# SuperCapV3Power.net
KiCad netlist of a schematic drawn in Altium Designer
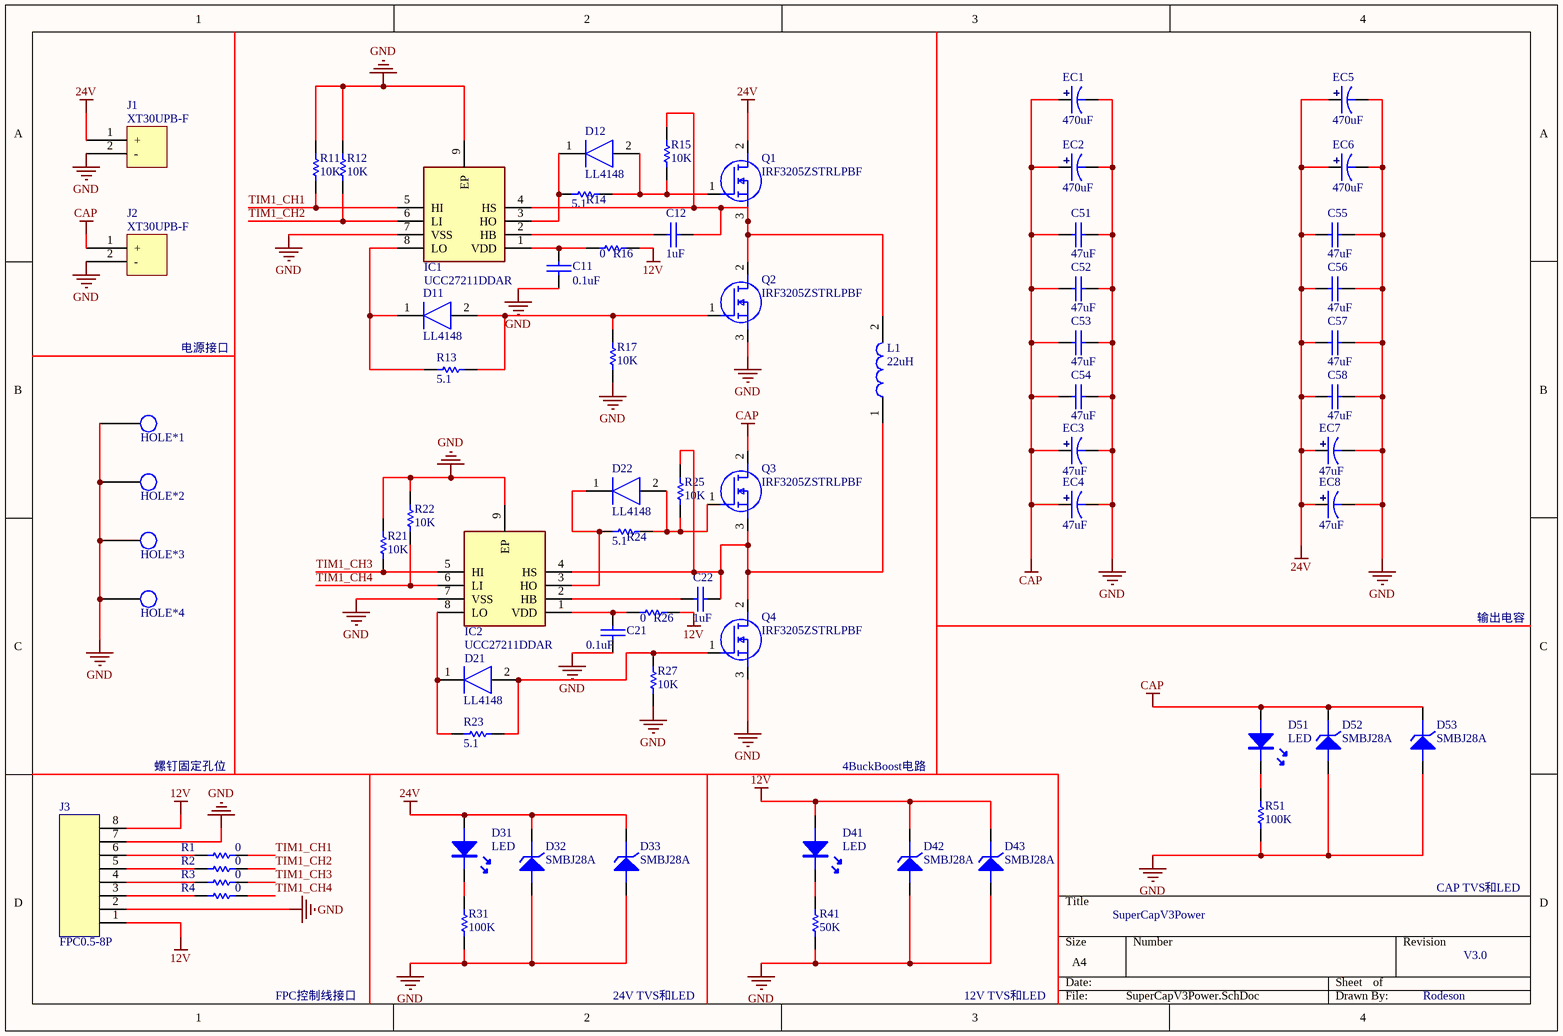
[diagram p0: SuperCapV3Power.SchDoc]

(export (version "E")
  (design (tool "Eeschema 10.0.6"))
  (components
    (comp (ref "C11")
      (value "0.1uF")
      (footprint "0603C")
      (description "无极性电容")
      (libsource (lib "电容") (part "CAP"))
    )
    (comp (ref "C12")
      (value "1uF")
      (footprint "0603C")
      (description "无极性电容")
      (libsource (lib "电容") (part "CAP"))
    )
    (comp (ref "C21")
      (value "0.1uF")
      (footprint "0603C")
      (description "无极性电容")
      (libsource (lib "电容") (part "CAP"))
    )
    (comp (ref "C22")
      (value "1uF")
      (footprint "0603C")
      (description "无极性电容")
      (libsource (lib "电容") (part "CAP"))
    )
    (comp (ref "C51")
      (value "47uF")
      (footprint "1812C")
      (description "无极性电容")
      (libsource (lib "电容") (part "CAP"))
    )
    (comp (ref "C52")
      (value "47uF")
      (footprint "1812C")
      (description "无极性电容")
      (libsource (lib "电容") (part "CAP"))
    )
    (comp (ref "C53")
      (value "47uF")
      (footprint "1812C")
      (description "无极性电容")
      (libsource (lib "电容") (part "CAP"))
    )
    (comp (ref "C54")
      (value "47uF")
      (footprint "1812C")
      (description "无极性电容")
      (libsource (lib "电容") (part "CAP"))
    )
    (comp (ref "C55")
      (value "47uF")
      (footprint "1812C")
      (description "无极性电容")
      (libsource (lib "电容") (part "CAP"))
    )
    (comp (ref "C56")
      (value "47uF")
      (footprint "1812C")
      (description "无极性电容")
      (libsource (lib "电容") (part "CAP"))
    )
    (comp (ref "C57")
      (value "47uF")
      (footprint "1812C")
      (description "无极性电容")
      (libsource (lib "电容") (part "CAP"))
    )
    (comp (ref "C58")
      (value "47uF")
      (footprint "1812C")
      (description "无极性电容")
      (libsource (lib "电容") (part "CAP"))
    )
    (comp (ref "D11")
      (value "LL4148")
      (footprint "SamacSys:FDLL4448")
      (description "Diode")
      (fields (field (name "MOUSER PART NUMBER") "512-LL4148"))
      (libsource (lib "*") (part "LL4148"))
    )
    (comp (ref "D12")
      (value "LL4148")
      (footprint "SamacSys:FDLL4448")
      (description "Diode")
      (fields (field (name "MOUSER PART NUMBER") "512-LL4148"))
      (libsource (lib "*") (part "LL4148"))
    )
    (comp (ref "D21")
      (value "LL4148")
      (footprint "SamacSys:FDLL4448")
      (description "Diode")
      (fields (field (name "MOUSER PART NUMBER") "512-LL4148"))
      (libsource (lib "*") (part "LL4148"))
    )
    (comp (ref "D22")
      (value "LL4148")
      (footprint "SamacSys:FDLL4448")
      (description "Diode")
      (fields (field (name "MOUSER PART NUMBER") "512-LL4148"))
      (libsource (lib "*") (part "LL4148"))
    )
    (comp (ref "D31") (value "LED") (footprint "LED-0603G") (libsource (lib "SuperCap_V2") (part "LED")))
    (comp (ref "D32")
      (value "SMBJ28A")
      (footprint "SMC/DO-214AB")
      (description "稳压二极管")
      (libsource (lib "二极管") (part "DIODE ZENER"))
    )
    (comp (ref "D33")
      (value "SMBJ28A")
      (footprint "SMC/DO-214AB")
      (description "稳压二极管")
      (libsource (lib "二极管") (part "DIODE ZENER"))
    )
    (comp (ref "D41") (value "LED") (footprint "LED-0603G") (libsource (lib "SuperCap_V2") (part "LED")))
    (comp (ref "D42")
      (value "SMBJ28A")
      (footprint "SMC/DO-214AB")
      (description "稳压二极管")
      (libsource (lib "二极管") (part "DIODE ZENER"))
    )
    (comp (ref "D43")
      (value "SMBJ28A")
      (footprint "SMC/DO-214AB")
      (description "稳压二极管")
      (libsource (lib "二极管") (part "DIODE ZENER"))
    )
    (comp (ref "D51") (value "LED") (footprint "LED-0603G") (libsource (lib "SuperCap_V2") (part "LED")))
    (comp (ref "D52")
      (value "SMBJ28A")
      (footprint "SMC/DO-214AB")
      (description "稳压二极管")
      (libsource (lib "二极管") (part "DIODE ZENER"))
    )
    (comp (ref "D53")
      (value "SMBJ28A")
      (footprint "SMC/DO-214AB")
      (description "稳压二极管")
      (libsource (lib "二极管") (part "DIODE ZENER"))
    )
    (comp (ref "EC1")
      (value "470uF")
      (footprint "DIP-EC5.0X10X16-A")
      (description "直插电解电容")
      (libsource (lib "电容") (part "DIP_ECAP"))
    )
    (comp (ref "EC2")
      (value "470uF")
      (footprint "DIP-EC5.0X10X16-A")
      (description "直插电解电容")
      (libsource (lib "电容") (part "DIP_ECAP"))
    )
    (comp (ref "EC3")
      (value "47uF")
      (footprint "SMD-EC10X10X10")
      (description "贴片电解电容")
      (libsource (lib "电容") (part "SMD_ECAP"))
    )
    (comp (ref "EC4")
      (value "47uF")
      (footprint "SMD-EC10X10X10")
      (description "贴片电解电容")
      (libsource (lib "电容") (part "SMD_ECAP"))
    )
    (comp (ref "EC5")
      (value "470uF")
      (footprint "DIP-EC5.0X10X16-A")
      (description "直插电解电容")
      (libsource (lib "电容") (part "DIP_ECAP"))
    )
    (comp (ref "EC6")
      (value "470uF")
      (footprint "DIP-EC5.0X10X16-A")
      (description "直插电解电容")
      (libsource (lib "电容") (part "DIP_ECAP"))
    )
    (comp (ref "EC7")
      (value "47uF")
      (footprint "SMD-EC10X10X10")
      (description "贴片电解电容")
      (libsource (lib "电容") (part "SMD_ECAP"))
    )
    (comp (ref "EC8")
      (value "47uF")
      (footprint "SMD-EC10X10X10")
      (description "贴片电解电容")
      (libsource (lib "电容") (part "SMD_ECAP"))
    )
    (comp (ref "HOLE*1") (value "Hole") (footprint "M3") (libsource (lib "SuperCap_V2") (part "Hole")))
    (comp (ref "HOLE*2") (value "Hole") (footprint "M3") (libsource (lib "SuperCap_V2") (part "Hole")))
    (comp (ref "HOLE*3") (value "Hole") (footprint "M3") (libsource (lib "SuperCap_V2") (part "Hole")))
    (comp (ref "HOLE*4") (value "Hole") (footprint "M3") (libsource (lib "SuperCap_V2") (part "Hole")))
    (comp (ref "IC1")
      (value "UCC27211DDAR")
      (footprint "SamacSys:SOIC127P600X170-9N")
      (description "Integrated Circuit")
      (fields (field (name "MOUSER PART NUMBER") "595-UCC27211DDAR"))
      (libsource (lib "SamacSys") (part "UCC27211DDAR"))
    )
    (comp (ref "IC2")
      (value "UCC27211DDAR")
      (footprint "SamacSys:SOIC127P600X170-9N")
      (description "Integrated Circuit")
      (fields (field (name "MOUSER PART NUMBER") "595-UCC27211DDAR"))
      (libsource (lib "SamacSys") (part "UCC27211DDAR"))
    )
    (comp (ref "J1")
      (value "XT30UPB-F")
      (footprint "XT30UPB-F")
      (libsource (lib "powerdesigner") (part "XT30UPB-F"))
    )
    (comp (ref "J2")
      (value "XT30UPB-F")
      (footprint "XT30UPB-F")
      (libsource (lib "powerdesigner") (part "XT30UPB-F"))
    )
    (comp (ref "J3")
      (value "FPC0.5-8P")
      (footprint "FPC0.5-8P")
      (description "贴片")
      (libsource (lib "FPC") (part "FPC0.5-8P"))
    )
    (comp (ref "L1")
      (value "22uH")
      (footprint "SamacSys:INDPM180170X700N")
      (description "Inductor")
      (fields (field (name "MANUFACTURER_PART_NUMBER") "BCIHP1770-100M"))
      (libsource (lib "SuperCap_V2") (part "BCIHP1770-100M"))
    )
    (comp (ref "Q1")
      (value "IRF3205ZSTRLPBF")
      (footprint "SamacSys:IDB30E60")
      (description "MOSFET (N-Channel)")
      (fields (field (name "MOUSER PART NUMBER") "942-IRF3205ZSTRLPBF"))
      (libsource (lib "SamacSys") (part "IRF3205ZSTRLPBF"))
    )
    (comp (ref "Q2")
      (value "IRF3205ZSTRLPBF")
      (footprint "SamacSys:IDB30E60")
      (description "MOSFET (N-Channel)")
      (fields (field (name "MOUSER PART NUMBER") "942-IRF3205ZSTRLPBF"))
      (libsource (lib "SamacSys") (part "IRF3205ZSTRLPBF"))
    )
    (comp (ref "Q3")
      (value "IRF3205ZSTRLPBF")
      (footprint "SamacSys:IDB30E60")
      (description "MOSFET (N-Channel)")
      (fields (field (name "MOUSER PART NUMBER") "942-IRF3205ZSTRLPBF"))
      (libsource (lib "SamacSys") (part "IRF3205ZSTRLPBF"))
    )
    (comp (ref "Q4")
      (value "IRF3205ZSTRLPBF")
      (footprint "SamacSys:IDB30E60")
      (description "MOSFET (N-Channel)")
      (fields (field (name "MOUSER PART NUMBER") "942-IRF3205ZSTRLPBF"))
      (libsource (lib "SamacSys") (part "IRF3205ZSTRLPBF"))
    )
    (comp (ref "R1") (value "0") (footprint "0603R") (libsource (lib "电阻") (part "RES")))
    (comp (ref "R2") (value "0") (footprint "0603R") (libsource (lib "电阻") (part "RES")))
    (comp (ref "R3") (value "0") (footprint "0603R") (libsource (lib "电阻") (part "RES")))
    (comp (ref "R4") (value "0") (footprint "0603R") (libsource (lib "电阻") (part "RES")))
    (comp (ref "R11") (value "10K") (footprint "0603R") (libsource (lib "电阻") (part "RES")))
    (comp (ref "R12") (value "10K") (footprint "0603R") (libsource (lib "电阻") (part "RES")))
    (comp (ref "R13") (value "5.1") (footprint "0603R") (libsource (lib "电阻") (part "RES")))
    (comp (ref "R14") (value "5.1") (footprint "0603R") (libsource (lib "电阻") (part "RES")))
    (comp (ref "R15") (value "10K") (footprint "0603R") (libsource (lib "电阻") (part "RES")))
    (comp (ref "R16") (value "0") (footprint "0603R") (libsource (lib "电阻") (part "RES")))
    (comp (ref "R17") (value "10K") (footprint "0603R") (libsource (lib "电阻") (part "RES")))
    (comp (ref "R21") (value "10K") (footprint "0603R") (libsource (lib "电阻") (part "RES")))
    (comp (ref "R22") (value "10K") (footprint "0603R") (libsource (lib "电阻") (part "RES")))
    (comp (ref "R23") (value "5.1") (footprint "0603R") (libsource (lib "电阻") (part "RES")))
    (comp (ref "R24") (value "5.1") (footprint "0603R") (libsource (lib "电阻") (part "RES")))
    (comp (ref "R25") (value "10K") (footprint "0603R") (libsource (lib "电阻") (part "RES")))
    (comp (ref "R26") (value "0") (footprint "0603R") (libsource (lib "电阻") (part "RES")))
    (comp (ref "R27") (value "10K") (footprint "0603R") (libsource (lib "电阻") (part "RES")))
    (comp (ref "R31") (value "100K") (footprint "0603R") (libsource (lib "电阻") (part "RES")))
    (comp (ref "R41") (value "50K") (footprint "0603R") (libsource (lib "电阻") (part "RES")))
    (comp (ref "R51") (value "100K") (footprint "0603R") (libsource (lib "电阻") (part "RES")))
  )
  (nets
    (net (code "1") (name "/TIM1_CH1") (class "Default")
      (node (ref "IC1") (pin "5") (pinfunction "HI_5") (pintype "passive"))
      (node (ref "R1") (pin "2") (pinfunction "2_2") (pintype "passive"))
      (node (ref "R11") (pin "1") (pinfunction "1_1") (pintype "passive"))
    )
    (net (code "2") (name "/TIM1_CH2") (class "Default")
      (node (ref "IC1") (pin "6") (pinfunction "LI_6") (pintype "passive"))
      (node (ref "R12") (pin "1") (pinfunction "1_1") (pintype "passive"))
      (node (ref "R2") (pin "2") (pinfunction "2_2") (pintype "passive"))
    )
    (net (code "3") (name "/TIM1_CH3") (class "Default")
      (node (ref "IC2") (pin "5") (pinfunction "HI_5") (pintype "passive"))
      (node (ref "R21") (pin "1") (pinfunction "1_1") (pintype "passive"))
      (node (ref "R3") (pin "2") (pinfunction "2_2") (pintype "passive"))
    )
    (net (code "4") (name "/TIM1_CH4") (class "Default")
      (node (ref "IC2") (pin "6") (pinfunction "LI_6") (pintype "passive"))
      (node (ref "R22") (pin "1") (pinfunction "1_1") (pintype "passive"))
      (node (ref "R4") (pin "2") (pinfunction "2_2") (pintype "passive"))
    )
    (net (code "5") (name "12V") (class "Default")
      (node (ref "D41") (pin "A") (pinfunction "A_A") (pintype "passive"))
      (node (ref "D42") (pin "K") (pinfunction "K_K") (pintype "passive"))
      (node (ref "D43") (pin "K") (pinfunction "K_K") (pintype "passive"))
      (node (ref "J3") (pin "1") (pinfunction "1_1") (pintype "passive"))
      (node (ref "J3") (pin "8") (pinfunction "8_8") (pintype "passive"))
      (node (ref "R16") (pin "2") (pinfunction "2_2") (pintype "passive"))
      (node (ref "R26") (pin "2") (pinfunction "2_2") (pintype "passive"))
    )
    (net (code "6") (name "24V") (class "Default")
      (node (ref "C55") (pin "1") (pinfunction "1_1") (pintype "passive"))
      (node (ref "C56") (pin "1") (pinfunction "1_1") (pintype "passive"))
      (node (ref "C57") (pin "1") (pinfunction "1_1") (pintype "passive"))
      (node (ref "C58") (pin "1") (pinfunction "1_1") (pintype "passive"))
      (node (ref "D31") (pin "A") (pinfunction "A_A") (pintype "passive"))
      (node (ref "D32") (pin "K") (pinfunction "K_K") (pintype "passive"))
      (node (ref "D33") (pin "K") (pinfunction "K_K") (pintype "passive"))
      (node (ref "EC5") (pin "1") (pinfunction "1_1") (pintype "passive"))
      (node (ref "EC6") (pin "1") (pinfunction "1_1") (pintype "passive"))
      (node (ref "EC7") (pin "1") (pinfunction "1_1") (pintype "passive"))
      (node (ref "EC8") (pin "1") (pinfunction "1_1") (pintype "passive"))
      (node (ref "J1") (pin "1") (pinfunction "+_1") (pintype "passive"))
      (node (ref "Q1") (pin "2") (pinfunction "D_2") (pintype "passive"))
    )
    (net (code "7") (name "CAP") (class "Default")
      (node (ref "C51") (pin "1") (pinfunction "1_1") (pintype "passive"))
      (node (ref "C52") (pin "1") (pinfunction "1_1") (pintype "passive"))
      (node (ref "C53") (pin "1") (pinfunction "1_1") (pintype "passive"))
      (node (ref "C54") (pin "1") (pinfunction "1_1") (pintype "passive"))
      (node (ref "D51") (pin "A") (pinfunction "A_A") (pintype "passive"))
      (node (ref "D52") (pin "K") (pinfunction "K_K") (pintype "passive"))
      (node (ref "D53") (pin "K") (pinfunction "K_K") (pintype "passive"))
      (node (ref "EC1") (pin "1") (pinfunction "1_1") (pintype "passive"))
      (node (ref "EC2") (pin "1") (pinfunction "1_1") (pintype "passive"))
      (node (ref "EC3") (pin "1") (pinfunction "1_1") (pintype "passive"))
      (node (ref "EC4") (pin "1") (pinfunction "1_1") (pintype "passive"))
      (node (ref "J2") (pin "1") (pinfunction "+_1") (pintype "passive"))
      (node (ref "Q3") (pin "2") (pinfunction "D_2") (pintype "passive"))
    )
    (net (code "8") (name "GND") (class "Default")
      (node (ref "C11") (pin "1") (pinfunction "1_1") (pintype "passive"))
      (node (ref "C21") (pin "1") (pinfunction "1_1") (pintype "passive"))
      (node (ref "C51") (pin "2") (pinfunction "2_2") (pintype "passive"))
      (node (ref "C52") (pin "2") (pinfunction "2_2") (pintype "passive"))
      (node (ref "C53") (pin "2") (pinfunction "2_2") (pintype "passive"))
      (node (ref "C54") (pin "2") (pinfunction "2_2") (pintype "passive"))
      (node (ref "C55") (pin "2") (pinfunction "2_2") (pintype "passive"))
      (node (ref "C56") (pin "2") (pinfunction "2_2") (pintype "passive"))
      (node (ref "C57") (pin "2") (pinfunction "2_2") (pintype "passive"))
      (node (ref "C58") (pin "2") (pinfunction "2_2") (pintype "passive"))
      (node (ref "D32") (pin "A") (pinfunction "A_A") (pintype "passive"))
      (node (ref "D33") (pin "A") (pinfunction "A_A") (pintype "passive"))
      (node (ref "D42") (pin "A") (pinfunction "A_A") (pintype "passive"))
      (node (ref "D43") (pin "A") (pinfunction "A_A") (pintype "passive"))
      (node (ref "D52") (pin "A") (pinfunction "A_A") (pintype "passive"))
      (node (ref "D53") (pin "A") (pinfunction "A_A") (pintype "passive"))
      (node (ref "EC1") (pin "2") (pinfunction "2_2") (pintype "passive"))
      (node (ref "EC2") (pin "2") (pinfunction "2_2") (pintype "passive"))
      (node (ref "EC3") (pin "2") (pinfunction "2_2") (pintype "passive"))
      (node (ref "EC4") (pin "2") (pinfunction "2_2") (pintype "passive"))
      (node (ref "EC5") (pin "2") (pinfunction "2_2") (pintype "passive"))
      (node (ref "EC6") (pin "2") (pinfunction "2_2") (pintype "passive"))
      (node (ref "EC7") (pin "2") (pinfunction "2_2") (pintype "passive"))
      (node (ref "EC8") (pin "2") (pinfunction "2_2") (pintype "passive"))
      (node (ref "HOLE*1") (pin "1") (pinfunction "1_1") (pintype "passive"))
      (node (ref "HOLE*2") (pin "1") (pinfunction "1_1") (pintype "passive"))
      (node (ref "HOLE*3") (pin "1") (pinfunction "1_1") (pintype "passive"))
      (node (ref "HOLE*4") (pin "1") (pinfunction "1_1") (pintype "passive"))
      (node (ref "IC1") (pin "7") (pinfunction "VSS_7") (pintype "passive"))
      (node (ref "IC1") (pin "9") (pinfunction "EP_9") (pintype "passive"))
      (node (ref "IC2") (pin "7") (pinfunction "VSS_7") (pintype "passive"))
      (node (ref "IC2") (pin "9") (pinfunction "EP_9") (pintype "passive"))
      (node (ref "J1") (pin "2") (pinfunction "-_2") (pintype "passive"))
      (node (ref "J2") (pin "2") (pinfunction "-_2") (pintype "passive"))
      (node (ref "J3") (pin "2") (pinfunction "2_2") (pintype "passive"))
      (node (ref "J3") (pin "7") (pinfunction "7_7") (pintype "passive"))
      (node (ref "Q2") (pin "3") (pinfunction "S_3") (pintype "passive"))
      (node (ref "Q4") (pin "3") (pinfunction "S_3") (pintype "passive"))
      (node (ref "R11") (pin "2") (pinfunction "2_2") (pintype "passive"))
      (node (ref "R12") (pin "2") (pinfunction "2_2") (pintype "passive"))
      (node (ref "R17") (pin "1") (pinfunction "1_1") (pintype "passive"))
      (node (ref "R21") (pin "2") (pinfunction "2_2") (pintype "passive"))
      (node (ref "R22") (pin "2") (pinfunction "2_2") (pintype "passive"))
      (node (ref "R27") (pin "1") (pinfunction "1_1") (pintype "passive"))
      (node (ref "R31") (pin "1") (pinfunction "1_1") (pintype "passive"))
      (node (ref "R41") (pin "1") (pinfunction "1_1") (pintype "passive"))
      (node (ref "R51") (pin "1") (pinfunction "1_1") (pintype "passive"))
    )
    (net (code "9") (name "Net-(D11-A)") (class "Default")
      (node (ref "D11") (pin "2") (pinfunction "A_2") (pintype "passive"))
      (node (ref "Q2") (pin "1") (pinfunction "G_1") (pintype "passive"))
      (node (ref "R13") (pin "2") (pinfunction "2_2") (pintype "passive"))
      (node (ref "R17") (pin "2") (pinfunction "2_2") (pintype "passive"))
    )
    (net (code "10") (name "Net-(D11-K)") (class "Default")
      (node (ref "D11") (pin "1") (pinfunction "K_1") (pintype "passive"))
      (node (ref "IC1") (pin "8") (pinfunction "LO_8") (pintype "passive"))
      (node (ref "R13") (pin "1") (pinfunction "1_1") (pintype "passive"))
    )
    (net (code "11") (name "Net-(D12-A)") (class "Default")
      (node (ref "D12") (pin "2") (pinfunction "A_2") (pintype "passive"))
      (node (ref "Q1") (pin "1") (pinfunction "G_1") (pintype "passive"))
      (node (ref "R14") (pin "2") (pinfunction "2_2") (pintype "passive"))
      (node (ref "R15") (pin "1") (pinfunction "1_1") (pintype "passive"))
    )
    (net (code "12") (name "Net-(D12-K)") (class "Default")
      (node (ref "D12") (pin "1") (pinfunction "K_1") (pintype "passive"))
      (node (ref "IC1") (pin "3") (pinfunction "HO_3") (pintype "passive"))
      (node (ref "R14") (pin "1") (pinfunction "1_1") (pintype "passive"))
    )
    (net (code "13") (name "Net-(D21-A)") (class "Default")
      (node (ref "D21") (pin "2") (pinfunction "A_2") (pintype "passive"))
      (node (ref "Q4") (pin "1") (pinfunction "G_1") (pintype "passive"))
      (node (ref "R23") (pin "2") (pinfunction "2_2") (pintype "passive"))
      (node (ref "R27") (pin "2") (pinfunction "2_2") (pintype "passive"))
    )
    (net (code "14") (name "Net-(D21-K)") (class "Default")
      (node (ref "D21") (pin "1") (pinfunction "K_1") (pintype "passive"))
      (node (ref "IC2") (pin "8") (pinfunction "LO_8") (pintype "passive"))
      (node (ref "R23") (pin "1") (pinfunction "1_1") (pintype "passive"))
    )
    (net (code "15") (name "Net-(D22-A)") (class "Default")
      (node (ref "D22") (pin "2") (pinfunction "A_2") (pintype "passive"))
      (node (ref "Q3") (pin "1") (pinfunction "G_1") (pintype "passive"))
      (node (ref "R24") (pin "2") (pinfunction "2_2") (pintype "passive"))
      (node (ref "R25") (pin "1") (pinfunction "1_1") (pintype "passive"))
    )
    (net (code "16") (name "Net-(D22-K)") (class "Default")
      (node (ref "D22") (pin "1") (pinfunction "K_1") (pintype "passive"))
      (node (ref "IC2") (pin "3") (pinfunction "HO_3") (pintype "passive"))
      (node (ref "R24") (pin "1") (pinfunction "1_1") (pintype "passive"))
    )
    (net (code "17") (name "Net-(D31-PadK)") (class "Default")
      (node (ref "D31") (pin "K") (pinfunction "K_K") (pintype "passive"))
      (node (ref "R31") (pin "2") (pinfunction "2_2") (pintype "passive"))
    )
    (net (code "18") (name "Net-(D41-PadK)") (class "Default")
      (node (ref "D41") (pin "K") (pinfunction "K_K") (pintype "passive"))
      (node (ref "R41") (pin "2") (pinfunction "2_2") (pintype "passive"))
    )
    (net (code "19") (name "Net-(D51-PadK)") (class "Default")
      (node (ref "D51") (pin "K") (pinfunction "K_K") (pintype "passive"))
      (node (ref "R51") (pin "2") (pinfunction "2_2") (pintype "passive"))
    )
    (net (code "20") (name "Net-(IC1-HB)") (class "Default")
      (node (ref "C12") (pin "2") (pinfunction "2_2") (pintype "passive"))
      (node (ref "IC1") (pin "2") (pinfunction "HB_2") (pintype "passive"))
    )
    (net (code "21") (name "Net-(IC1-HS)") (class "Default")
      (node (ref "C12") (pin "1") (pinfunction "1_1") (pintype "passive"))
      (node (ref "IC1") (pin "4") (pinfunction "HS_4") (pintype "passive"))
      (node (ref "L1") (pin "2") (pinfunction "2_2") (pintype "passive"))
      (node (ref "Q1") (pin "3") (pinfunction "S_3") (pintype "passive"))
      (node (ref "Q2") (pin "2") (pinfunction "D_2") (pintype "passive"))
      (node (ref "R15") (pin "2") (pinfunction "2_2") (pintype "passive"))
    )
    (net (code "22") (name "Net-(IC1-VDD)") (class "Default")
      (node (ref "C11") (pin "2") (pinfunction "2_2") (pintype "passive"))
      (node (ref "IC1") (pin "1") (pinfunction "VDD_1") (pintype "passive"))
      (node (ref "R16") (pin "1") (pinfunction "1_1") (pintype "passive"))
    )
    (net (code "23") (name "Net-(IC2-HB)") (class "Default")
      (node (ref "C22") (pin "2") (pinfunction "2_2") (pintype "passive"))
      (node (ref "IC2") (pin "2") (pinfunction "HB_2") (pintype "passive"))
    )
    (net (code "24") (name "Net-(IC2-HS)") (class "Default")
      (node (ref "C22") (pin "1") (pinfunction "1_1") (pintype "passive"))
      (node (ref "IC2") (pin "4") (pinfunction "HS_4") (pintype "passive"))
      (node (ref "L1") (pin "1") (pinfunction "1_1") (pintype "passive"))
      (node (ref "Q3") (pin "3") (pinfunction "S_3") (pintype "passive"))
      (node (ref "Q4") (pin "2") (pinfunction "D_2") (pintype "passive"))
      (node (ref "R25") (pin "2") (pinfunction "2_2") (pintype "passive"))
    )
    (net (code "25") (name "Net-(IC2-VDD)") (class "Default")
      (node (ref "C21") (pin "2") (pinfunction "2_2") (pintype "passive"))
      (node (ref "IC2") (pin "1") (pinfunction "VDD_1") (pintype "passive"))
      (node (ref "R26") (pin "1") (pinfunction "1_1") (pintype "passive"))
    )
    (net (code "26") (name "Net-(J3-Pad3)") (class "Default")
      (node (ref "J3") (pin "3") (pinfunction "3_3") (pintype "passive"))
      (node (ref "R4") (pin "1") (pinfunction "1_1") (pintype "passive"))
    )
    (net (code "27") (name "Net-(J3-Pad4)") (class "Default")
      (node (ref "J3") (pin "4") (pinfunction "4_4") (pintype "passive"))
      (node (ref "R3") (pin "1") (pinfunction "1_1") (pintype "passive"))
    )
    (net (code "28") (name "Net-(J3-Pad5)") (class "Default")
      (node (ref "J3") (pin "5") (pinfunction "5_5") (pintype "passive"))
      (node (ref "R2") (pin "1") (pinfunction "1_1") (pintype "passive"))
    )
    (net (code "29") (name "Net-(J3-Pad6)") (class "Default")
      (node (ref "J3") (pin "6") (pinfunction "6_6") (pintype "passive"))
      (node (ref "R1") (pin "1") (pinfunction "1_1") (pintype "passive"))
    )
  )
)
